# LL_project.net
KiCad netlist of a schematic drawn in Altium Designer
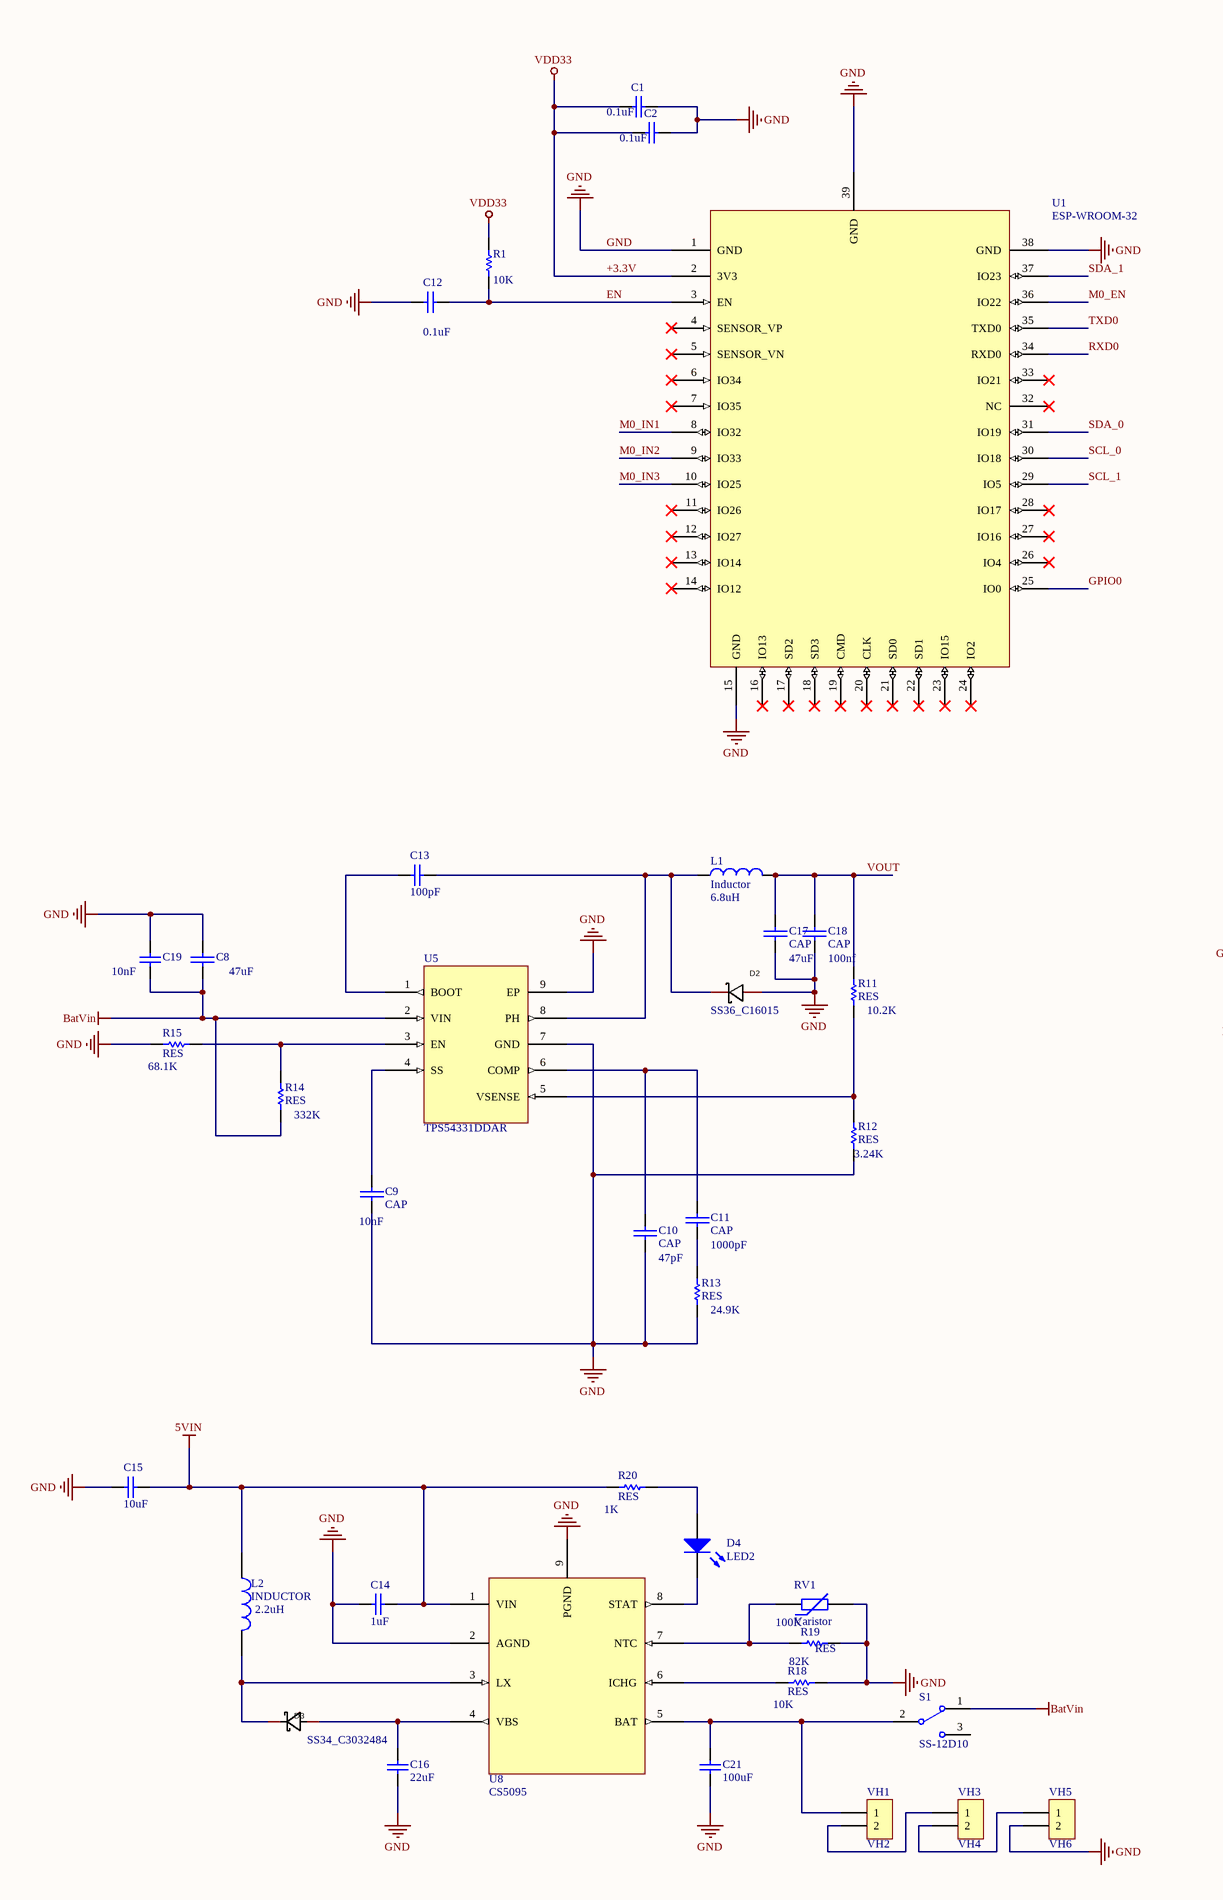
[diagram p0: LL_project.SchDoc, left]
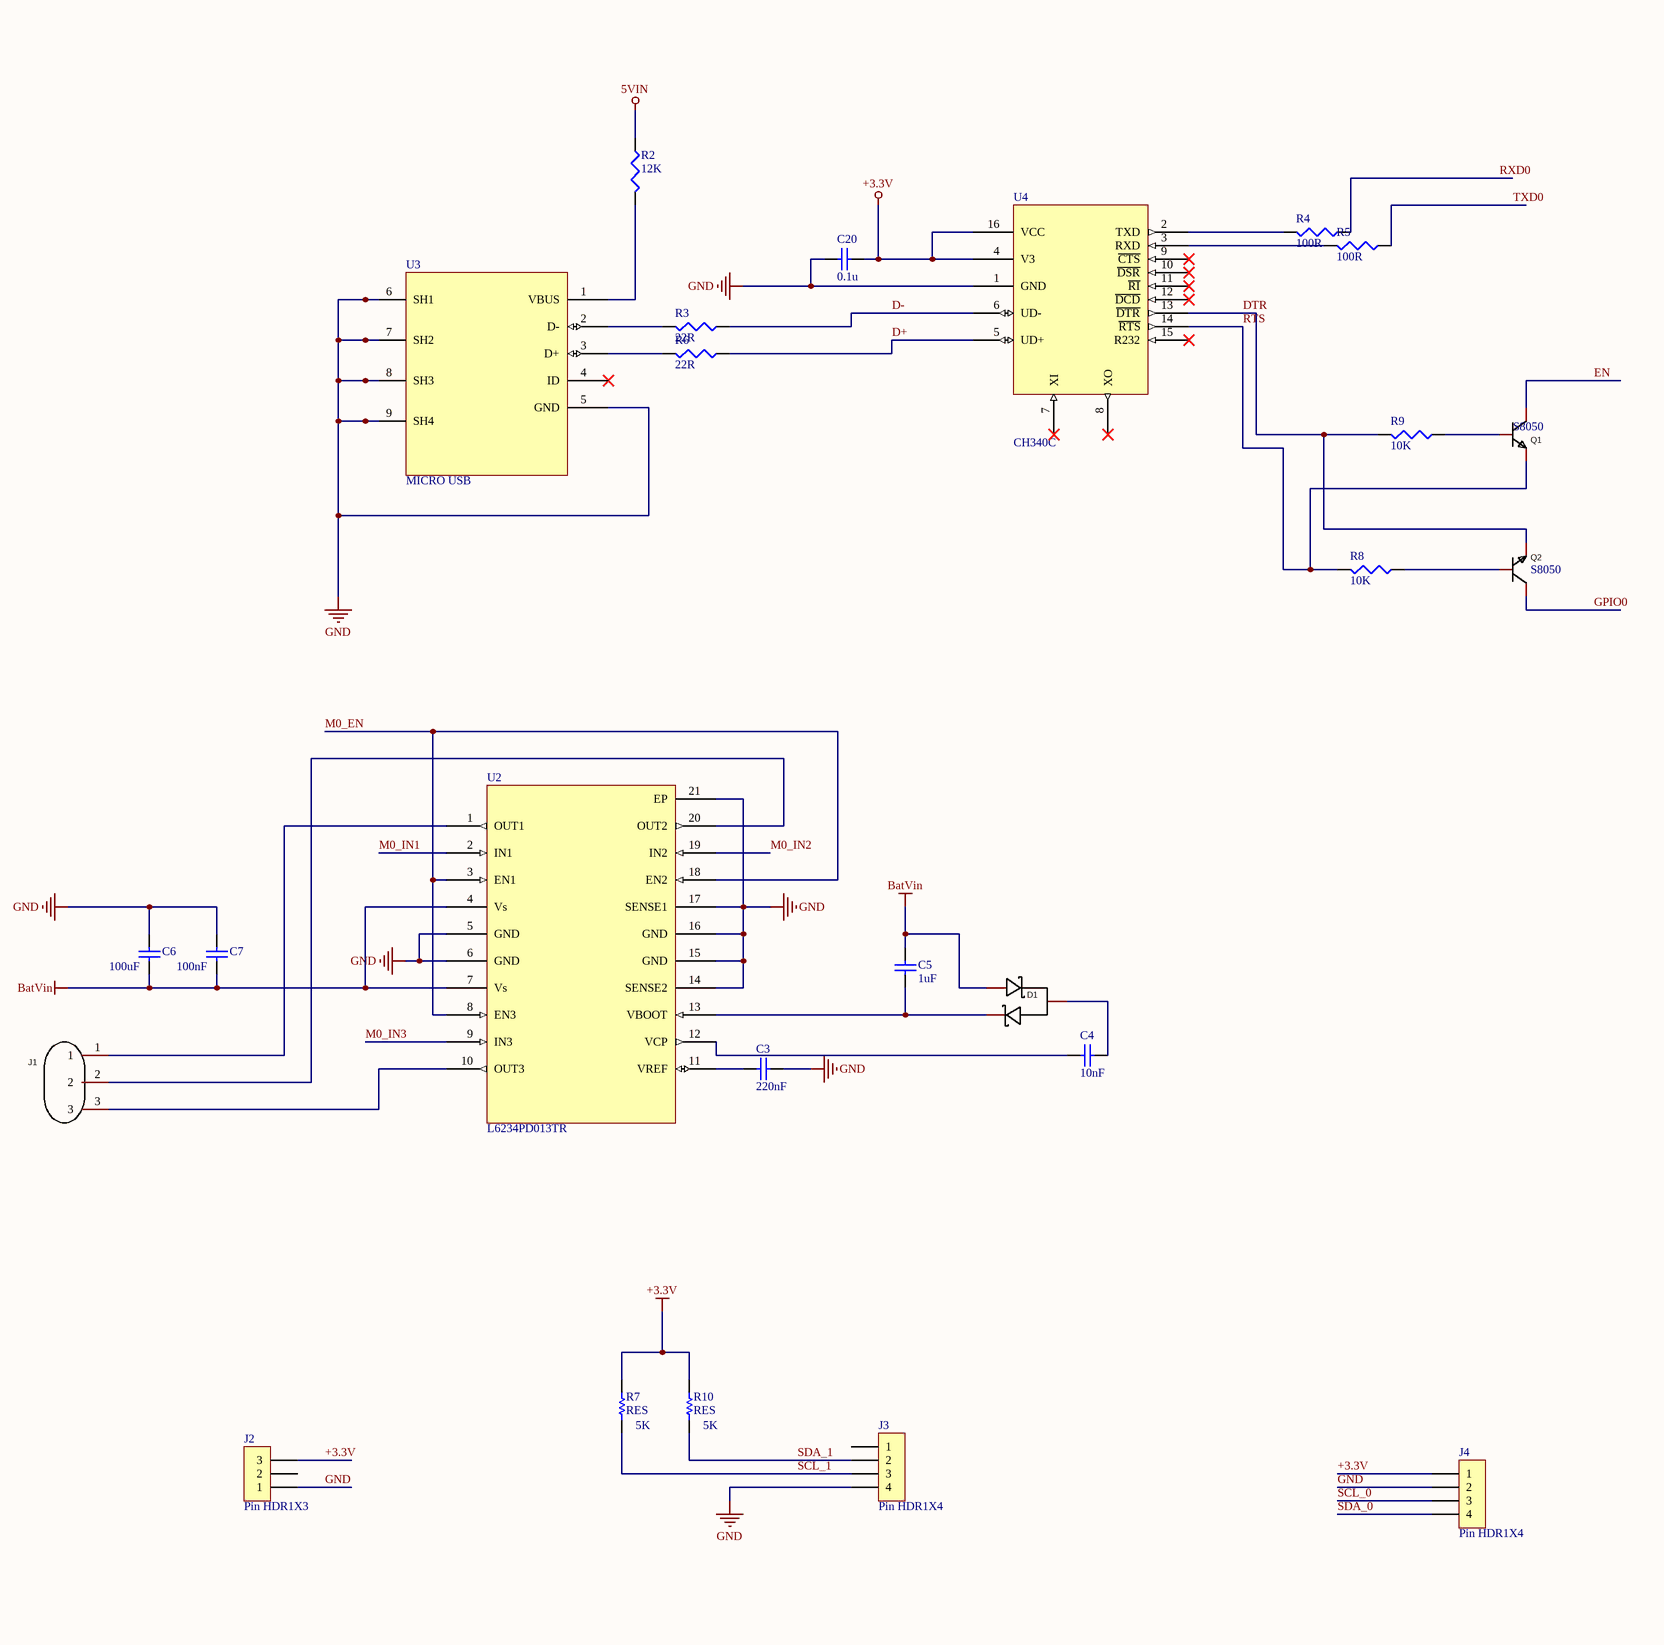
[diagram p1: LL_project.SchDoc, right]

(export (version "E")
  (design (tool "Eeschema 10.0.6"))
  (components
    (comp (ref "C1")
      (value "0.1uF")
      (footprint "HanPCB:0603-1")
      (description "Capacitor (Semiconductor SIM Model)")
      (fields (field (name "Comment") "Cap Semi") (field (name "PUBLISHER") "Altium Limited"))
      (libsource (lib "Miscellaneous Devices") (part "Cap Semi"))
    )
    (comp (ref "C2")
      (value "0.1uF")
      (footprint "HanPCB:0603-1")
      (description "Capacitor (Semiconductor SIM Model)")
      (fields (field (name "Comment") "Cap Semi") (field (name "PUBLISHER") "Altium Limited"))
      (libsource (lib "Miscellaneous Devices") (part "Cap Semi"))
    )
    (comp (ref "C3")
      (value "220nF")
      (footprint "HanPCB:0603-1")
      (description "Capacitor (Semiconductor SIM Model)")
      (fields (field (name "Comment") "Cap Semi") (field (name "PUBLISHER") "Altium Limited"))
      (libsource (lib "Miscellaneous Devices") (part "Cap Semi"))
    )
    (comp (ref "C4")
      (value "10nF")
      (footprint "HanPCB:0603-1")
      (description "Capacitor (Semiconductor SIM Model)")
      (fields (field (name "Comment") "Cap Semi") (field (name "PUBLISHER") "Altium Limited"))
      (libsource (lib "Miscellaneous Devices") (part "Cap Semi"))
    )
    (comp (ref "C5")
      (value "1uF")
      (footprint "HanPCB:0603-1")
      (description "Capacitor (Semiconductor SIM Model)")
      (fields (field (name "Comment") "Cap Semi") (field (name "PUBLISHER") "Altium Limited"))
      (libsource (lib "Miscellaneous Devices") (part "Cap Semi"))
    )
    (comp (ref "C6")
      (value "100uF")
      (footprint "HanPCB:0603-1")
      (description "Capacitor (Semiconductor SIM Model)")
      (fields (field (name "Comment") "Cap Semi") (field (name "PUBLISHER") "Altium Limited"))
      (libsource (lib "Miscellaneous Devices") (part "Cap Semi"))
    )
    (comp (ref "C7")
      (value "100nF")
      (footprint "HanPCB:0603-1")
      (description "Capacitor (Semiconductor SIM Model)")
      (fields (field (name "Comment") "Cap Semi") (field (name "PUBLISHER") "Altium Limited"))
      (libsource (lib "Miscellaneous Devices") (part "Cap Semi"))
    )
    (comp (ref "C8")
      (value "CAP")
      (footprint "HanPCB:0603-1")
      (description "无极性电容")
      (fields (field (name "ALTIUM_UNNAMED_1") "47uF"))
      (libsource (lib "电容") (part "CAP"))
    )
    (comp (ref "C9")
      (value "CAP")
      (footprint "HanPCB:0603-1")
      (description "无极性电容")
      (fields (field (name "ALTIUM_UNNAMED_1") "10nF"))
      (libsource (lib "电容") (part "CAP"))
    )
    (comp (ref "C10")
      (value "CAP")
      (footprint "HanPCB:0603-1")
      (description "无极性电容")
      (fields (field (name "ALTIUM_UNNAMED_1") "47pF"))
      (libsource (lib "电容") (part "CAP"))
    )
    (comp (ref "C11")
      (value "CAP")
      (footprint "HanPCB:0603-1")
      (description "无极性电容")
      (fields (field (name "ALTIUM_UNNAMED_1") "1000pF"))
      (libsource (lib "电容") (part "CAP"))
    )
    (comp (ref "C12")
      (value "0.1uF")
      (footprint "HanPCB:0603-1")
      (description "Capacitor (Semiconductor SIM Model)")
      (fields (field (name "Comment") "Cap Semi") (field (name "PUBLISHER") "Altium Limited"))
      (libsource (lib "Miscellaneous Devices") (part "Cap Semi"))
    )
    (comp (ref "C13")
      (value "100pF")
      (footprint "HanPCB:0603-1")
      (description "Capacitor (Semiconductor SIM Model)")
      (fields (field (name "Comment") "Cap Semi") (field (name "PUBLISHER") "Altium Limited"))
      (libsource (lib "Miscellaneous Devices") (part "Cap Semi"))
    )
    (comp (ref "C14")
      (value "1uF")
      (footprint "HanPCB:0603-1")
      (description "Capacitor (Semiconductor SIM Model)")
      (fields (field (name "Comment") "Cap Semi") (field (name "PUBLISHER") "Altium Limited"))
      (libsource (lib "Miscellaneous Devices") (part "Cap Semi"))
    )
    (comp (ref "C15")
      (value "10uF")
      (footprint "HanPCB:0603-1")
      (description "Capacitor (Semiconductor SIM Model)")
      (fields (field (name "Comment") "Cap Semi") (field (name "PUBLISHER") "Altium Limited"))
      (libsource (lib "Miscellaneous Devices") (part "Cap Semi"))
    )
    (comp (ref "C16")
      (value "22uF")
      (footprint "HanPCB:0603-1")
      (description "Capacitor (Semiconductor SIM Model)")
      (fields (field (name "Comment") "Cap Semi") (field (name "PUBLISHER") "Altium Limited"))
      (libsource (lib "Miscellaneous Devices") (part "Cap Semi"))
    )
    (comp (ref "C17")
      (value "CAP")
      (footprint "HanPCB:0603-1")
      (description "无极性电容")
      (fields (field (name "ALTIUM_UNNAMED_1") "47uF"))
      (libsource (lib "电容") (part "CAP"))
    )
    (comp (ref "C18")
      (value "CAP")
      (footprint "HanPCB:0603-1")
      (description "无极性电容")
      (fields (field (name "ALTIUM_UNNAMED_1") "100nf"))
      (libsource (lib "电容") (part "CAP"))
    )
    (comp (ref "C19")
      (value "10nF")
      (footprint "HanPCB:0603-1")
      (description "Capacitor (Semiconductor SIM Model)")
      (fields (field (name "Comment") "Cap Semi") (field (name "PUBLISHER") "Altium Limited"))
      (libsource (lib "Miscellaneous Devices") (part "Cap Semi"))
    )
    (comp (ref "C20")
      (value "0.1u")
      (footprint "HanPCB:0603-1")
      (description "Capacitor (Semiconductor SIM Model)")
      (fields (field (name "Comment") "Cap Semi") (field (name "PUBLISHER") "Altium Limited"))
      (libsource (lib "Miscellaneous Devices") (part "Cap Semi"))
    )
    (comp (ref "C21")
      (value "100uF")
      (footprint "HanPCB:0603-1")
      (description "Capacitor (Semiconductor SIM Model)")
      (fields (field (name "Comment") "Cap Semi") (field (name "PUBLISHER") "Altium Limited"))
      (libsource (lib "Miscellaneous Devices") (part "Cap Semi"))
    )
    (comp (ref "D1")
      (value "LBAT54SLT1G")
      (footprint "schottky")
      (fields (field (name "MANUFACTURER") "LRC(乐山无线电)"))
      (libsource (lib "altium-import") (part "root_0_LBAT54SLT1G_"))
    )
    (comp (ref "D2")
      (value "SS36_C16015")
      (footprint "SMA_L4.3-W2.6-LS5.2-RD")
      (fields (field (name "MANUFACTURER") "MDD") (field (name "MANUFACTURER PART") "SS36"))
      (libsource (lib "altium-import") (part "root_0_SS36_C16015_"))
    )
    (comp (ref "D3")
      (value "SS34_C3032484")
      (footprint "SMA_L4.3-W2.6-LS5.2-RD")
      (fields (field (name "MANUFACTURER") "TDD(台冠电子)") (field (name "MANUFACTURER PART") "SS34"))
      (libsource (lib "altium-import") (part "root_0_SS34_C3032484_"))
    )
    (comp (ref "D4")
      (value "LED2")
      (footprint "LED_0603_R")
      (description "Typical RED, GREEN, YELLOW, AMBER GaAs LED")
      (fields (field (name "PUBLISHER") "Altium Limited"))
      (libsource (lib "Miscellaneous Devices") (part "LED2"))
    )
    (comp (ref "J1")
      (value "WJ126V-5.0-3P")
      (footprint "CONN-TH_3P-P5.00_WJ126V-5.0-3P")
      (fields (field (name "MANUFACTURER") "KANGNEX(康奈克斯电气)"))
      (libsource (lib "altium-import") (part "root_0_WJ126V-5.0-3P_"))
    )
    (comp (ref "J2")
      (value "Pin HDR1X3")
      (footprint "Pin HDR1X3/2.54mm-S")
      (libsource (lib "排针") (part "Pin HDR1X3"))
    )
    (comp (ref "J3")
      (value "Pin HDR1X4")
      (footprint "Pin HDR1X4/2.54mm-S")
      (libsource (lib "排针") (part "Pin HDR1X4"))
    )
    (comp (ref "J4")
      (value "Pin HDR1X4")
      (footprint "Pin HDR1X4/2.54mm-S")
      (libsource (lib "排针") (part "Pin HDR1X4"))
    )
    (comp (ref "L1")
      (value "Inductor")
      (footprint "0805L")
      (fields (field (name "ALTIUM_VALUE") "6.8uH") (field (name "PUBLISHER") "Altium Limited"))
      (libsource (lib "Miscellaneous Devices") (part "Inductor"))
    )
    (comp (ref "L2")
      (value "INDUCTOR")
      (footprint "0603L")
      (fields (field (name "ALTIUM_UNNAMED_1") "2.2uH"))
      (libsource (lib "电感") (part "INDUCTOR"))
    )
    (comp (ref "Q1")
      (value "S8050")
      (footprint "Q1")
      (fields (field (name "MANUFACTURER") "Doeshare(德芯)"))
      (libsource (lib "LL_project") (part "S8050"))
    )
    (comp (ref "Q2")
      (value "S8050")
      (footprint "Q1")
      (fields (field (name "MANUFACTURER") "Doeshare(德芯)"))
      (libsource (lib "LL_project") (part "S8050"))
    )
    (comp (ref "R1")
      (value "10K")
      (footprint "HanPCB:0603-1")
      (description "Resistor")
      (fields (field (name "Comment") "Res1") (field (name "PUBLISHER") "Altium Limited"))
      (libsource (lib "Miscellaneous Devices") (part "Res1"))
    )
    (comp (ref "R2")
      (value "12K")
      (footprint "0805-1")
      (description "Resistor")
      (fields (field (name "Comment") "Res3") (field (name "PUBLISHER") "Altium Limited"))
      (libsource (lib "Miscellaneous Devices") (part "Res3"))
    )
    (comp (ref "R3")
      (value "22R")
      (footprint "HanPCB:0603-1")
      (description "Resistor")
      (fields (field (name "Comment") "Res3") (field (name "PUBLISHER") "Altium Limited"))
      (libsource (lib "Miscellaneous Devices") (part "Res3"))
    )
    (comp (ref "R4")
      (value "100R")
      (footprint "HanPCB:0603-1")
      (description "Resistor")
      (fields (field (name "Comment") "Res3") (field (name "PUBLISHER") "Altium Limited"))
      (libsource (lib "Miscellaneous Devices") (part "Res3"))
    )
    (comp (ref "R5")
      (value "100R")
      (footprint "HanPCB:0603-1")
      (description "Resistor")
      (fields (field (name "Comment") "Res3") (field (name "PUBLISHER") "Altium Limited"))
      (libsource (lib "Miscellaneous Devices") (part "Res3"))
    )
    (comp (ref "R6")
      (value "22R")
      (footprint "HanPCB:0603-1")
      (description "Resistor")
      (fields (field (name "Comment") "Res3") (field (name "PUBLISHER") "Altium Limited"))
      (libsource (lib "Miscellaneous Devices") (part "Res3"))
    )
    (comp (ref "R7")
      (value "RES")
      (footprint "HanPCB:0603-1")
      (fields (field (name "ALTIUM_UNNAMED_1") "5K"))
      (libsource (lib "电阻") (part "RES"))
    )
    (comp (ref "R8")
      (value "10K")
      (footprint "HanPCB:0603-1")
      (description "Resistor")
      (fields (field (name "Comment") "Res3") (field (name "PUBLISHER") "Altium Limited"))
      (libsource (lib "Miscellaneous Devices") (part "Res3"))
    )
    (comp (ref "R9")
      (value "10K")
      (footprint "HanPCB:0603-1")
      (description "Resistor")
      (fields (field (name "Comment") "Res3") (field (name "PUBLISHER") "Altium Limited"))
      (libsource (lib "Miscellaneous Devices") (part "Res3"))
    )
    (comp (ref "R10")
      (value "RES")
      (footprint "HanPCB:0603-1")
      (fields (field (name "ALTIUM_UNNAMED_1") "5K"))
      (libsource (lib "电阻") (part "RES"))
    )
    (comp (ref "R11")
      (value "RES")
      (footprint "HanPCB:0603-1")
      (fields (field (name "ALTIUM_UNNAMED_1") "10.2K"))
      (libsource (lib "电阻") (part "RES"))
    )
    (comp (ref "R12")
      (value "RES")
      (footprint "HanPCB:0603-1")
      (fields (field (name "ALTIUM_UNNAMED_1") "3.24K"))
      (libsource (lib "电阻") (part "RES"))
    )
    (comp (ref "R13")
      (value "RES")
      (footprint "HanPCB:0603-1")
      (fields (field (name "ALTIUM_UNNAMED_1") "24.9K"))
      (libsource (lib "电阻") (part "RES"))
    )
    (comp (ref "R14")
      (value "RES")
      (footprint "HanPCB:0603-1")
      (fields (field (name "ALTIUM_UNNAMED_1") "332K"))
      (libsource (lib "电阻") (part "RES"))
    )
    (comp (ref "R15")
      (value "RES")
      (footprint "HanPCB:0603-1")
      (fields (field (name "ALTIUM_UNNAMED_1") "68.1K"))
      (libsource (lib "电阻") (part "RES"))
    )
    (comp (ref "R18")
      (value "RES")
      (footprint "HanPCB:0603-1")
      (fields (field (name "ALTIUM_UNNAMED_1") "10K"))
      (libsource (lib "电阻") (part "RES"))
    )
    (comp (ref "R19")
      (value "RES")
      (footprint "HanPCB:0603-1")
      (fields (field (name "ALTIUM_UNNAMED_1") "82K"))
      (libsource (lib "电阻") (part "RES"))
    )
    (comp (ref "R20")
      (value "RES")
      (footprint "HanPCB:0603-1")
      (fields (field (name "ALTIUM_UNNAMED_1") "1K"))
      (libsource (lib "电阻") (part "RES"))
    )
    (comp (ref "RV1")
      (value "Varistor")
      (footprint "HanPCB:0603-1")
      (description "压敏电阻")
      (fields (field (name "ALTIUM_UNNAMED_1") "100K"))
      (libsource (lib "电阻") (part "Varistor"))
    )
    (comp (ref "S1") (value "SS-12D10") (footprint "SS-12D10") (libsource (lib "电源开关") (part "SS-12D10")))
    (comp (ref "U1")
      (value "ESP-WROOM-32")
      (footprint "ESP32")
      (libsource (lib "LL_project") (part "ESP-WROOM-32"))
    )
    (comp (ref "U2")
      (value "L6234PD013TR")
      (footprint "L6234")
      (libsource (lib "LL_project") (part "L6234PD013TR"))
    )
    (comp (ref "U3")
      (value "MICRO USB")
      (footprint "MICRO-USB-SMD_MICROXNJ")
      (libsource (lib "LL_project") (part "MICRO USB"))
    )
    (comp (ref "U4")
      (value "CH340C")
      (footprint "SOP-16_L10.0-W3.9-P1.27-LS6.0-BL")
      (libsource (lib "LL_project") (part "CH340C"))
    )
    (comp (ref "U5")
      (value "TPS54331DDAR")
      (footprint "SOIC-8_L5.0-W4.0-P1.27-LS6.0-BL-EP2.0")
      (libsource (lib "LL_project") (part "TPS54331DDAR"))
    )
    (comp (ref "U8") (value "CS5095") (footprint "cs5095") (libsource (lib "LL_project") (part "CS5095")))
    (comp (ref "VH1") (value "VH2") (footprint "VH") (libsource (lib "XH，VH") (part "VH2")))
    (comp (ref "VH3") (value "VH4") (footprint "VH") (libsource (lib "XH，VH") (part "VH2")))
    (comp (ref "VH5") (value "VH6") (footprint "VH") (libsource (lib "XH，VH") (part "VH2")))
  )
  (nets
    (net (code "1") (name "+3.3V") (class "Default")
      (node (ref "C1") (pin "1") (pinfunction "1_1") (pintype "passive"))
      (node (ref "C2") (pin "1") (pinfunction "1_1") (pintype "passive"))
      (node (ref "C20") (pin "1") (pinfunction "1_1") (pintype "passive"))
      (node (ref "J2") (pin "3") (pinfunction "3_3") (pintype "passive"))
      (node (ref "J4") (pin "1") (pinfunction "1_1") (pintype "passive"))
      (node (ref "R1") (pin "2") (pinfunction "2_2") (pintype "passive"))
      (node (ref "R10") (pin "2") (pinfunction "2_2") (pintype "passive"))
      (node (ref "R7") (pin "2") (pinfunction "2_2") (pintype "passive"))
      (node (ref "U1") (pin "2") (pinfunction "3V3_2") (pintype "power_in"))
      (node (ref "U4") (pin "16") (pinfunction "VCC_16") (pintype "power_in"))
      (node (ref "U4") (pin "4") (pinfunction "V3_4") (pintype "power_in"))
    )
    (net (code "2") (name "/D+") (class "Default")
      (node (ref "R6") (pin "1") (pinfunction "1_1") (pintype "passive"))
      (node (ref "U4") (pin "5") (pinfunction "UD+_5") (pintype "bidirectional"))
    )
    (net (code "3") (name "/D-") (class "Default")
      (node (ref "R3") (pin "1") (pinfunction "1_1") (pintype "passive"))
      (node (ref "U4") (pin "6") (pinfunction "UD-_6") (pintype "bidirectional"))
    )
    (net (code "4") (name "/DTR") (class "Default")
      (node (ref "Q2") (pin "2") (pinfunction "E_2") (pintype "passive"))
      (node (ref "R9") (pin "2") (pinfunction "2_2") (pintype "passive"))
      (node (ref "U4") (pin "13") (pinfunction "~{DTR}_13") (pintype "output"))
    )
    (net (code "5") (name "/EN") (class "Default")
      (node (ref "C12") (pin "2") (pinfunction "2_2") (pintype "passive"))
      (node (ref "Q1") (pin "3") (pinfunction "C_3") (pintype "passive"))
      (node (ref "R1") (pin "1") (pinfunction "1_1") (pintype "passive"))
      (node (ref "U1") (pin "3") (pinfunction "EN_3") (pintype "input"))
    )
    (net (code "6") (name "/GPIO0") (class "Default")
      (node (ref "Q2") (pin "3") (pinfunction "C_3") (pintype "passive"))
      (node (ref "U1") (pin "25") (pinfunction "IO0_25") (pintype "bidirectional"))
    )
    (net (code "7") (name "/M0_EN") (class "Default")
      (node (ref "U1") (pin "36") (pinfunction "IO22_36") (pintype "bidirectional"))
      (node (ref "U2") (pin "18") (pinfunction "EN2_18") (pintype "input"))
      (node (ref "U2") (pin "3") (pinfunction "EN1_3") (pintype "input"))
      (node (ref "U2") (pin "8") (pinfunction "EN3_8") (pintype "input"))
    )
    (net (code "8") (name "/M0_IN1") (class "Default")
      (node (ref "U1") (pin "8") (pinfunction "IO32_8") (pintype "bidirectional"))
      (node (ref "U2") (pin "2") (pinfunction "IN1_2") (pintype "input"))
    )
    (net (code "9") (name "/M0_IN2") (class "Default")
      (node (ref "U1") (pin "9") (pinfunction "IO33_9") (pintype "bidirectional"))
      (node (ref "U2") (pin "19") (pinfunction "IN2_19") (pintype "input"))
    )
    (net (code "10") (name "/M0_IN3") (class "Default")
      (node (ref "U1") (pin "10") (pinfunction "IO25_10") (pintype "bidirectional"))
      (node (ref "U2") (pin "9") (pinfunction "IN3_9") (pintype "input"))
    )
    (net (code "11") (name "/RTS") (class "Default")
      (node (ref "Q1") (pin "2") (pinfunction "E_2") (pintype "passive"))
      (node (ref "R8") (pin "2") (pinfunction "2_2") (pintype "passive"))
      (node (ref "U4") (pin "14") (pinfunction "~{RTS}_14") (pintype "output"))
    )
    (net (code "12") (name "/RXD0") (class "Default")
      (node (ref "R4") (pin "1") (pinfunction "1_1") (pintype "passive"))
      (node (ref "U1") (pin "34") (pinfunction "RXD0_34") (pintype "bidirectional"))
    )
    (net (code "13") (name "/SCL_0") (class "Default")
      (node (ref "J4") (pin "3") (pinfunction "3_3") (pintype "passive"))
      (node (ref "U1") (pin "30") (pinfunction "IO18_30") (pintype "bidirectional"))
    )
    (net (code "14") (name "/SCL_1") (class "Default")
      (node (ref "J3") (pin "3") (pinfunction "3_3") (pintype "passive"))
      (node (ref "R7") (pin "1") (pinfunction "1_1") (pintype "passive"))
      (node (ref "U1") (pin "29") (pinfunction "IO5_29") (pintype "bidirectional"))
    )
    (net (code "15") (name "/SDA_0") (class "Default")
      (node (ref "J4") (pin "4") (pinfunction "4_4") (pintype "passive"))
      (node (ref "U1") (pin "31") (pinfunction "IO19_31") (pintype "bidirectional"))
    )
    (net (code "16") (name "/SDA_1") (class "Default")
      (node (ref "J3") (pin "2") (pinfunction "2_2") (pintype "passive"))
      (node (ref "R10") (pin "1") (pinfunction "1_1") (pintype "passive"))
      (node (ref "U1") (pin "37") (pinfunction "IO23_37") (pintype "bidirectional"))
    )
    (net (code "17") (name "/TXD0") (class "Default")
      (node (ref "R5") (pin "1") (pinfunction "1_1") (pintype "passive"))
      (node (ref "U1") (pin "35") (pinfunction "TXD0_35") (pintype "bidirectional"))
    )
    (net (code "18") (name "/VOUT") (class "Default")
      (node (ref "C17") (pin "2") (pinfunction "2_2") (pintype "passive"))
      (node (ref "C18") (pin "2") (pinfunction "2_2") (pintype "passive"))
      (node (ref "L1") (pin "2") (pinfunction "2_2") (pintype "passive"))
      (node (ref "R11") (pin "2") (pinfunction "2_2") (pintype "passive"))
    )
    (net (code "19") (name "5VIN") (class "Default")
      (node (ref "C14") (pin "2") (pinfunction "2_2") (pintype "passive"))
      (node (ref "C15") (pin "2") (pinfunction "2_2") (pintype "passive"))
      (node (ref "L2") (pin "1") (pinfunction "1_1") (pintype "passive"))
      (node (ref "R2") (pin "1") (pinfunction "1_1") (pintype "passive"))
      (node (ref "R20") (pin "2") (pinfunction "2_2") (pintype "passive"))
      (node (ref "U8") (pin "1") (pinfunction "VIN_1") (pintype "power_in"))
    )
    (net (code "20") (name "BatVin") (class "Default")
      (node (ref "C19") (pin "1") (pinfunction "1_1") (pintype "passive"))
      (node (ref "C5") (pin "1") (pinfunction "1_1") (pintype "passive"))
      (node (ref "C6") (pin "1") (pinfunction "1_1") (pintype "passive"))
      (node (ref "C7") (pin "1") (pinfunction "1_1") (pintype "passive"))
      (node (ref "C8") (pin "1") (pinfunction "1_1") (pintype "passive"))
      (node (ref "D1") (pin "1") (pinfunction "A_1") (pintype "passive"))
      (node (ref "R14") (pin "1") (pinfunction "1_1") (pintype "passive"))
      (node (ref "S1") (pin "1") (pinfunction "1_1") (pintype "passive"))
      (node (ref "U2") (pin "4") (pinfunction "Vs_4") (pintype "power_in"))
      (node (ref "U2") (pin "7") (pinfunction "Vs_7") (pintype "power_in"))
      (node (ref "U5") (pin "2") (pinfunction "VIN_2") (pintype "input"))
    )
    (net (code "21") (name "GND") (class "Default")
      (node (ref "C1") (pin "2") (pinfunction "2_2") (pintype "passive"))
      (node (ref "C10") (pin "1") (pinfunction "1_1") (pintype "passive"))
      (node (ref "C12") (pin "1") (pinfunction "1_1") (pintype "passive"))
      (node (ref "C14") (pin "1") (pinfunction "1_1") (pintype "passive"))
      (node (ref "C15") (pin "1") (pinfunction "1_1") (pintype "passive"))
      (node (ref "C16") (pin "1") (pinfunction "1_1") (pintype "passive"))
      (node (ref "C17") (pin "1") (pinfunction "1_1") (pintype "passive"))
      (node (ref "C18") (pin "1") (pinfunction "1_1") (pintype "passive"))
      (node (ref "C19") (pin "2") (pinfunction "2_2") (pintype "passive"))
      (node (ref "C2") (pin "2") (pinfunction "2_2") (pintype "passive"))
      (node (ref "C20") (pin "2") (pinfunction "2_2") (pintype "passive"))
      (node (ref "C21") (pin "1") (pinfunction "1_1") (pintype "passive"))
      (node (ref "C3") (pin "1") (pinfunction "1_1") (pintype "passive"))
      (node (ref "C6") (pin "2") (pinfunction "2_2") (pintype "passive"))
      (node (ref "C7") (pin "2") (pinfunction "2_2") (pintype "passive"))
      (node (ref "C8") (pin "2") (pinfunction "2_2") (pintype "passive"))
      (node (ref "C9") (pin "1") (pinfunction "1_1") (pintype "passive"))
      (node (ref "D2") (pin "2") (pinfunction "A_2") (pintype "passive"))
      (node (ref "J2") (pin "1") (pinfunction "1_1") (pintype "passive"))
      (node (ref "J3") (pin "4") (pinfunction "4_4") (pintype "passive"))
      (node (ref "J4") (pin "2") (pinfunction "2_2") (pintype "passive"))
      (node (ref "R12") (pin "1") (pinfunction "1_1") (pintype "passive"))
      (node (ref "R13") (pin "1") (pinfunction "1_1") (pintype "passive"))
      (node (ref "R15") (pin "2") (pinfunction "2_2") (pintype "passive"))
      (node (ref "R18") (pin "1") (pinfunction "1_1") (pintype "passive"))
      (node (ref "R19") (pin "1") (pinfunction "1_1") (pintype "passive"))
      (node (ref "RV1") (pin "2") (pinfunction "2_2") (pintype "passive"))
      (node (ref "U1") (pin "1") (pinfunction "GND_1") (pintype "power_in"))
      (node (ref "U1") (pin "15") (pinfunction "GND_15") (pintype "passive"))
      (node (ref "U1") (pin "38") (pinfunction "GND_38") (pintype "passive"))
      (node (ref "U1") (pin "39") (pinfunction "GND_39") (pintype "passive"))
      (node (ref "U2") (pin "14") (pinfunction "SENSE2_14") (pintype "passive"))
      (node (ref "U2") (pin "15") (pinfunction "GND_15") (pintype "passive"))
      (node (ref "U2") (pin "16") (pinfunction "GND_16") (pintype "passive"))
      (node (ref "U2") (pin "17") (pinfunction "SENSE1_17") (pintype "passive"))
      (node (ref "U2") (pin "21") (pinfunction "EP_21") (pintype "passive"))
      (node (ref "U2") (pin "5") (pinfunction "GND_5") (pintype "passive"))
      (node (ref "U2") (pin "6") (pinfunction "GND_6") (pintype "passive"))
      (node (ref "U3") (pin "5") (pinfunction "GND_5") (pintype "power_in"))
      (node (ref "U3") (pin "6") (pinfunction "SH1_6") (pintype "passive"))
      (node (ref "U3") (pin "7") (pinfunction "SH2_7") (pintype "passive"))
      (node (ref "U3") (pin "8") (pinfunction "SH3_8") (pintype "passive"))
      (node (ref "U3") (pin "9") (pinfunction "SH4_9") (pintype "passive"))
      (node (ref "U4") (pin "1") (pinfunction "GND_1") (pintype "power_in"))
      (node (ref "U5") (pin "7") (pinfunction "GND_7") (pintype "power_in"))
      (node (ref "U5") (pin "9") (pinfunction "EP_9") (pintype "passive"))
      (node (ref "U8") (pin "2") (pinfunction "AGND_2") (pintype "power_in"))
      (node (ref "U8") (pin "9") (pinfunction "PGND_9") (pintype "power_in"))
      (node (ref "VH5") (pin "2") (pinfunction "2_2") (pintype "passive"))
    )
    (net (code "22") (name "Net-(C11-Pad1)") (class "Default")
      (node (ref "C11") (pin "1") (pinfunction "1_1") (pintype "passive"))
      (node (ref "R13") (pin "2") (pinfunction "2_2") (pintype "passive"))
    )
    (net (code "23") (name "Net-(D1-AK)") (class "Default")
      (node (ref "C4") (pin "1") (pinfunction "1_1") (pintype "passive"))
      (node (ref "D1") (pin "3") (pinfunction "AK_3") (pintype "passive"))
    )
    (net (code "24") (name "Net-(D1-K)") (class "Default")
      (node (ref "C5") (pin "2") (pinfunction "2_2") (pintype "passive"))
      (node (ref "D1") (pin "2") (pinfunction "K_2") (pintype "passive"))
      (node (ref "U2") (pin "13") (pinfunction "VBOOT_13") (pintype "input"))
    )
    (net (code "25") (name "Net-(D2-K)") (class "Default")
      (node (ref "C13") (pin "2") (pinfunction "2_2") (pintype "passive"))
      (node (ref "D2") (pin "1") (pinfunction "K_1") (pintype "passive"))
      (node (ref "L1") (pin "1") (pinfunction "1_1") (pintype "passive"))
      (node (ref "U5") (pin "8") (pinfunction "PH_8") (pintype "output"))
    )
    (net (code "26") (name "Net-(D3-A)") (class "Default")
      (node (ref "C16") (pin "2") (pinfunction "2_2") (pintype "passive"))
      (node (ref "D3") (pin "2") (pinfunction "A_2") (pintype "passive"))
      (node (ref "U8") (pin "4") (pinfunction "VBS_4") (pintype "output"))
    )
    (net (code "27") (name "Net-(D3-K)") (class "Default")
      (node (ref "D3") (pin "1") (pinfunction "K_1") (pintype "passive"))
      (node (ref "L2") (pin "2") (pinfunction "2_2") (pintype "passive"))
      (node (ref "U8") (pin "3") (pinfunction "LX_3") (pintype "input"))
    )
    (net (code "28") (name "Net-(D4-A)") (class "Default")
      (node (ref "D4") (pin "1") (pinfunction "A_1") (pintype "passive"))
      (node (ref "R20") (pin "1") (pinfunction "1_1") (pintype "passive"))
    )
    (net (code "29") (name "Net-(D4-K)") (class "Default")
      (node (ref "D4") (pin "2") (pinfunction "K_2") (pintype "passive"))
      (node (ref "U8") (pin "8") (pinfunction "STAT_8") (pintype "output"))
    )
    (net (code "30") (name "Net-(Q1-B)") (class "Default")
      (node (ref "Q1") (pin "1") (pinfunction "B_1") (pintype "passive"))
      (node (ref "R9") (pin "1") (pinfunction "1_1") (pintype "passive"))
    )
    (net (code "31") (name "Net-(Q2-B)") (class "Default")
      (node (ref "Q2") (pin "1") (pinfunction "B_1") (pintype "passive"))
      (node (ref "R8") (pin "1") (pinfunction "1_1") (pintype "passive"))
    )
    (net (code "32") (name "Net-(U2-OUT1)") (class "Default")
      (node (ref "J1") (pin "1") (pinfunction "1_1") (pintype "passive"))
      (node (ref "U2") (pin "1") (pinfunction "OUT1_1") (pintype "output"))
    )
    (net (code "33") (name "Net-(U2-OUT2)") (class "Default")
      (node (ref "J1") (pin "2") (pinfunction "2_2") (pintype "passive"))
      (node (ref "U2") (pin "20") (pinfunction "OUT2_20") (pintype "output"))
    )
    (net (code "34") (name "Net-(U2-OUT3)") (class "Default")
      (node (ref "J1") (pin "3") (pinfunction "3_3") (pintype "passive"))
      (node (ref "U2") (pin "10") (pinfunction "OUT3_10") (pintype "output"))
    )
    (net (code "35") (name "Net-(U2-VCP)") (class "Default")
      (node (ref "C4") (pin "2") (pinfunction "2_2") (pintype "passive"))
      (node (ref "U2") (pin "12") (pinfunction "VCP_12") (pintype "output"))
    )
    (net (code "36") (name "Net-(U2-VREF)") (class "Default")
      (node (ref "C3") (pin "2") (pinfunction "2_2") (pintype "passive"))
      (node (ref "U2") (pin "11") (pinfunction "VREF_11") (pintype "bidirectional"))
    )
    (net (code "37") (name "Net-(U3-D+)") (class "Default")
      (node (ref "R6") (pin "2") (pinfunction "2_2") (pintype "passive"))
      (node (ref "U3") (pin "3") (pinfunction "D+_3") (pintype "bidirectional"))
    )
    (net (code "38") (name "Net-(U3-D-)") (class "Default")
      (node (ref "R3") (pin "2") (pinfunction "2_2") (pintype "passive"))
      (node (ref "U3") (pin "2") (pinfunction "D-_2") (pintype "bidirectional"))
    )
    (net (code "39") (name "Net-(U3-VBUS)") (class "Default")
      (node (ref "R2") (pin "2") (pinfunction "2_2") (pintype "passive"))
      (node (ref "U3") (pin "1") (pinfunction "VBUS_1") (pintype "power_in"))
    )
    (net (code "40") (name "Net-(U4-RXD)") (class "Default")
      (node (ref "R5") (pin "2") (pinfunction "2_2") (pintype "passive"))
      (node (ref "U4") (pin "3") (pinfunction "RXD_3") (pintype "input"))
    )
    (net (code "41") (name "Net-(U4-TXD)") (class "Default")
      (node (ref "R4") (pin "2") (pinfunction "2_2") (pintype "passive"))
      (node (ref "U4") (pin "2") (pinfunction "TXD_2") (pintype "output"))
    )
    (net (code "42") (name "Net-(U5-BOOT)") (class "Default")
      (node (ref "C13") (pin "1") (pinfunction "1_1") (pintype "passive"))
      (node (ref "U5") (pin "1") (pinfunction "BOOT_1") (pintype "output"))
    )
    (net (code "43") (name "Net-(U5-COMP)") (class "Default")
      (node (ref "C10") (pin "2") (pinfunction "2_2") (pintype "passive"))
      (node (ref "C11") (pin "2") (pinfunction "2_2") (pintype "passive"))
      (node (ref "U5") (pin "6") (pinfunction "COMP_6") (pintype "output"))
    )
    (net (code "44") (name "Net-(U5-EN)") (class "Default")
      (node (ref "R14") (pin "2") (pinfunction "2_2") (pintype "passive"))
      (node (ref "R15") (pin "1") (pinfunction "1_1") (pintype "passive"))
      (node (ref "U5") (pin "3") (pinfunction "EN_3") (pintype "input"))
    )
    (net (code "45") (name "Net-(U5-SS)") (class "Default")
      (node (ref "C9") (pin "2") (pinfunction "2_2") (pintype "passive"))
      (node (ref "U5") (pin "4") (pinfunction "SS_4") (pintype "input"))
    )
    (net (code "46") (name "Net-(U5-VSENSE)") (class "Default")
      (node (ref "R11") (pin "1") (pinfunction "1_1") (pintype "passive"))
      (node (ref "R12") (pin "2") (pinfunction "2_2") (pintype "passive"))
      (node (ref "U5") (pin "5") (pinfunction "VSENSE_5") (pintype "input"))
    )
    (net (code "47") (name "Net-(U8-BAT)") (class "Default")
      (node (ref "C21") (pin "2") (pinfunction "2_2") (pintype "passive"))
      (node (ref "S1") (pin "2") (pinfunction "2_2") (pintype "passive"))
      (node (ref "U8") (pin "5") (pinfunction "BAT_5") (pintype "output"))
      (node (ref "VH1") (pin "1") (pinfunction "1_1") (pintype "passive"))
    )
    (net (code "48") (name "Net-(U8-ICHG)") (class "Default")
      (node (ref "R18") (pin "2") (pinfunction "2_2") (pintype "passive"))
      (node (ref "U8") (pin "6") (pinfunction "ICHG_6") (pintype "input"))
    )
    (net (code "49") (name "Net-(U8-NTC)") (class "Default")
      (node (ref "R19") (pin "2") (pinfunction "2_2") (pintype "passive"))
      (node (ref "RV1") (pin "1") (pinfunction "1_1") (pintype "passive"))
      (node (ref "U8") (pin "7") (pinfunction "NTC_7") (pintype "input"))
    )
    (net (code "50") (name "Net-(VH1-Pad2)") (class "Default")
      (node (ref "VH1") (pin "2") (pinfunction "2_2") (pintype "passive"))
      (node (ref "VH3") (pin "1") (pinfunction "1_1") (pintype "passive"))
    )
    (net (code "51") (name "Net-(VH3-Pad2)") (class "Default")
      (node (ref "VH3") (pin "2") (pinfunction "2_2") (pintype "passive"))
      (node (ref "VH5") (pin "1") (pinfunction "1_1") (pintype "passive"))
    )
    (net (code "52") (name "unconnected-(J2-Pad2)") (class "Default")
      (node (ref "J2") (pin "2") (pinfunction "2_2") (pintype "passive"))
    )
    (net (code "53") (name "unconnected-(J3-Pad1)") (class "Default")
      (node (ref "J3") (pin "1") (pinfunction "1_1") (pintype "passive"))
    )
    (net (code "54") (name "unconnected-(S1-Pad3)") (class "Default")
      (node (ref "S1") (pin "3") (pinfunction "3_3") (pintype "passive"))
    )
    (net (code "55") (name "unconnected-(U1-CLK-Pad20)") (class "Default")
      (node (ref "U1") (pin "20") (pinfunction "CLK_20") (pintype "bidirectional+no_connect"))
    )
    (net (code "56") (name "unconnected-(U1-CMD-Pad19)") (class "Default")
      (node (ref "U1") (pin "19") (pinfunction "CMD_19") (pintype "bidirectional+no_connect"))
    )
    (net (code "57") (name "unconnected-(U1-IO2-Pad24)") (class "Default")
      (node (ref "U1") (pin "24") (pinfunction "IO2_24") (pintype "bidirectional+no_connect"))
    )
    (net (code "58") (name "unconnected-(U1-IO4-Pad26)") (class "Default")
      (node (ref "U1") (pin "26") (pinfunction "IO4_26") (pintype "bidirectional+no_connect"))
    )
    (net (code "59") (name "unconnected-(U1-IO12-Pad14)") (class "Default")
      (node (ref "U1") (pin "14") (pinfunction "IO12_14") (pintype "bidirectional+no_connect"))
    )
    (net (code "60") (name "unconnected-(U1-IO13-Pad16)") (class "Default")
      (node (ref "U1") (pin "16") (pinfunction "IO13_16") (pintype "bidirectional+no_connect"))
    )
    (net (code "61") (name "unconnected-(U1-IO14-Pad13)") (class "Default")
      (node (ref "U1") (pin "13") (pinfunction "IO14_13") (pintype "bidirectional+no_connect"))
    )
    (net (code "62") (name "unconnected-(U1-IO15-Pad23)") (class "Default")
      (node (ref "U1") (pin "23") (pinfunction "IO15_23") (pintype "bidirectional+no_connect"))
    )
    (net (code "63") (name "unconnected-(U1-IO16-Pad27)") (class "Default")
      (node (ref "U1") (pin "27") (pinfunction "IO16_27") (pintype "bidirectional+no_connect"))
    )
    (net (code "64") (name "unconnected-(U1-IO17-Pad28)") (class "Default")
      (node (ref "U1") (pin "28") (pinfunction "IO17_28") (pintype "bidirectional+no_connect"))
    )
    (net (code "65") (name "unconnected-(U1-IO21-Pad33)") (class "Default")
      (node (ref "U1") (pin "33") (pinfunction "IO21_33") (pintype "bidirectional+no_connect"))
    )
    (net (code "66") (name "unconnected-(U1-IO26-Pad11)") (class "Default")
      (node (ref "U1") (pin "11") (pinfunction "IO26_11") (pintype "bidirectional+no_connect"))
    )
    (net (code "67") (name "unconnected-(U1-IO27-Pad12)") (class "Default")
      (node (ref "U1") (pin "12") (pinfunction "IO27_12") (pintype "bidirectional+no_connect"))
    )
    (net (code "68") (name "unconnected-(U1-IO34-Pad6)") (class "Default")
      (node (ref "U1") (pin "6") (pinfunction "IO34_6") (pintype "input+no_connect"))
    )
    (net (code "69") (name "unconnected-(U1-IO35-Pad7)") (class "Default")
      (node (ref "U1") (pin "7") (pinfunction "IO35_7") (pintype "input+no_connect"))
    )
    (net (code "70") (name "unconnected-(U1-NC-Pad32)") (class "Default")
      (node (ref "U1") (pin "32") (pinfunction "NC_32") (pintype "passive+no_connect"))
    )
    (net (code "71") (name "unconnected-(U1-SD0-Pad21)") (class "Default")
      (node (ref "U1") (pin "21") (pinfunction "SD0_21") (pintype "bidirectional+no_connect"))
    )
    (net (code "72") (name "unconnected-(U1-SD1-Pad22)") (class "Default")
      (node (ref "U1") (pin "22") (pinfunction "SD1_22") (pintype "bidirectional+no_connect"))
    )
    (net (code "73") (name "unconnected-(U1-SD2-Pad17)") (class "Default")
      (node (ref "U1") (pin "17") (pinfunction "SD2_17") (pintype "bidirectional+no_connect"))
    )
    (net (code "74") (name "unconnected-(U1-SD3-Pad18)") (class "Default")
      (node (ref "U1") (pin "18") (pinfunction "SD3_18") (pintype "bidirectional+no_connect"))
    )
    (net (code "75") (name "unconnected-(U1-SENSOR_VN-Pad5)") (class "Default")
      (node (ref "U1") (pin "5") (pinfunction "SENSOR_VN_5") (pintype "input+no_connect"))
    )
    (net (code "76") (name "unconnected-(U1-SENSOR_VP-Pad4)") (class "Default")
      (node (ref "U1") (pin "4") (pinfunction "SENSOR_VP_4") (pintype "input+no_connect"))
    )
    (net (code "77") (name "unconnected-(U3-ID-Pad4)") (class "Default")
      (node (ref "U3") (pin "4") (pinfunction "ID_4") (pintype "passive+no_connect"))
    )
    (net (code "78") (name "unconnected-(U4-R232-Pad15)") (class "Default")
      (node (ref "U4") (pin "15") (pinfunction "R232_15") (pintype "input+no_connect"))
    )
    (net (code "79") (name "unconnected-(U4-XI-Pad7)") (class "Default")
      (node (ref "U4") (pin "7") (pinfunction "XI_7") (pintype "input+no_connect"))
    )
    (net (code "80") (name "unconnected-(U4-XO-Pad8)") (class "Default")
      (node (ref "U4") (pin "8") (pinfunction "XO_8") (pintype "output+no_connect"))
    )
    (net (code "81") (name "unconnected-(U4-~{CTS}-Pad9)") (class "Default")
      (node (ref "U4") (pin "9") (pinfunction "~{CTS}_9") (pintype "input+no_connect"))
    )
    (net (code "82") (name "unconnected-(U4-~{DCD}-Pad12)") (class "Default")
      (node (ref "U4") (pin "12") (pinfunction "~{DCD}_12") (pintype "input+no_connect"))
    )
    (net (code "83") (name "unconnected-(U4-~{DSR}-Pad10)") (class "Default")
      (node (ref "U4") (pin "10") (pinfunction "~{DSR}_10") (pintype "input+no_connect"))
    )
    (net (code "84") (name "unconnected-(U4-~{RI}-Pad11)") (class "Default")
      (node (ref "U4") (pin "11") (pinfunction "~{RI}_11") (pintype "input+no_connect"))
    )
  )
)
